# Schematic.net
KiCad netlist of a schematic drawn in EAGLE
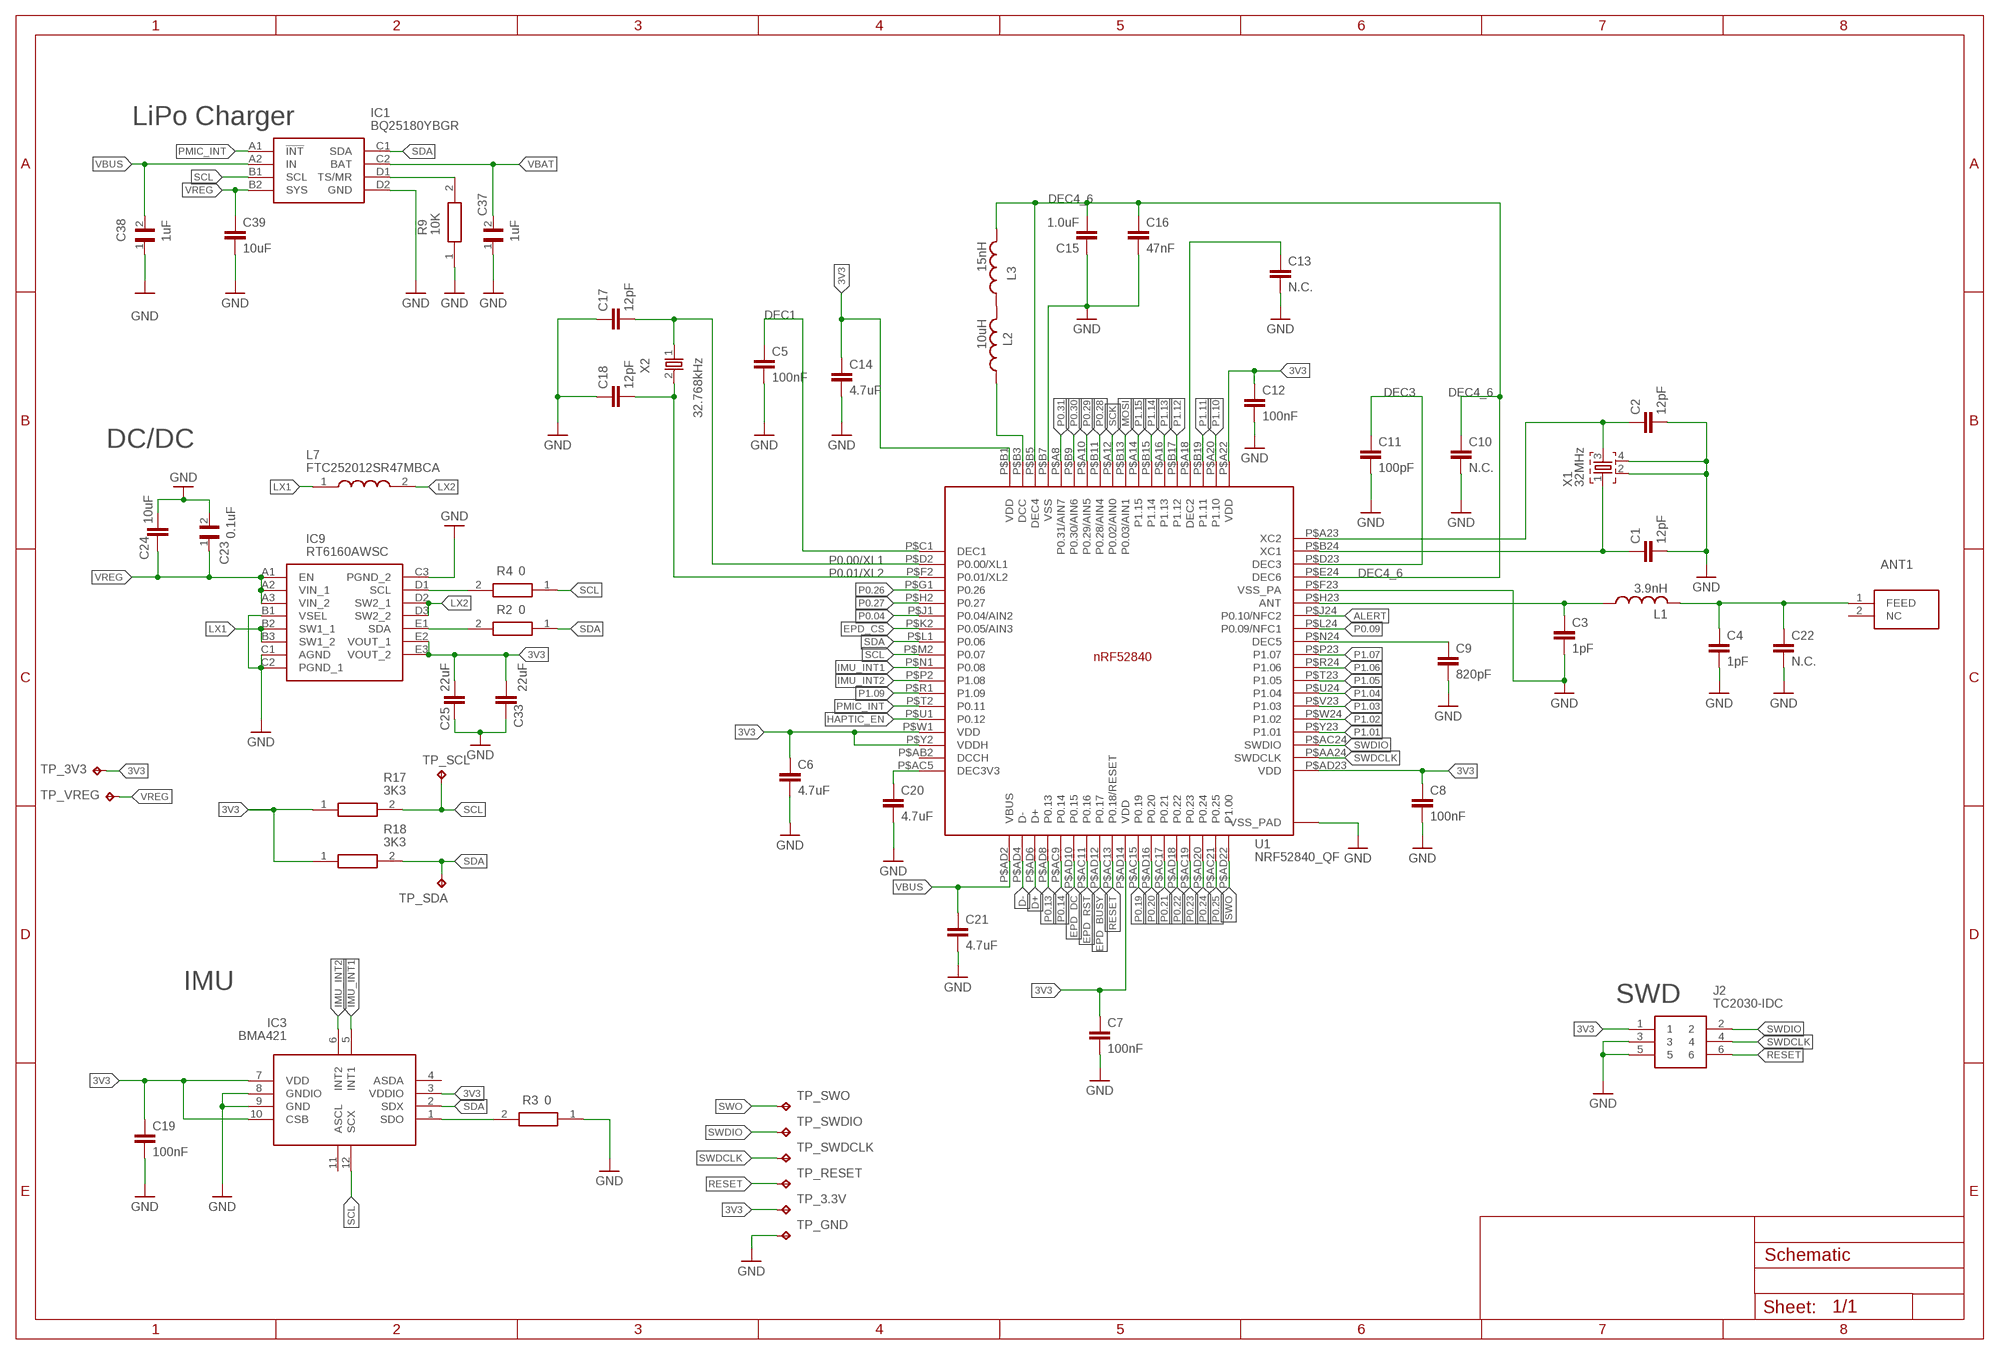
[diagram p0: schematic, sheet 1, part 1 of 2]
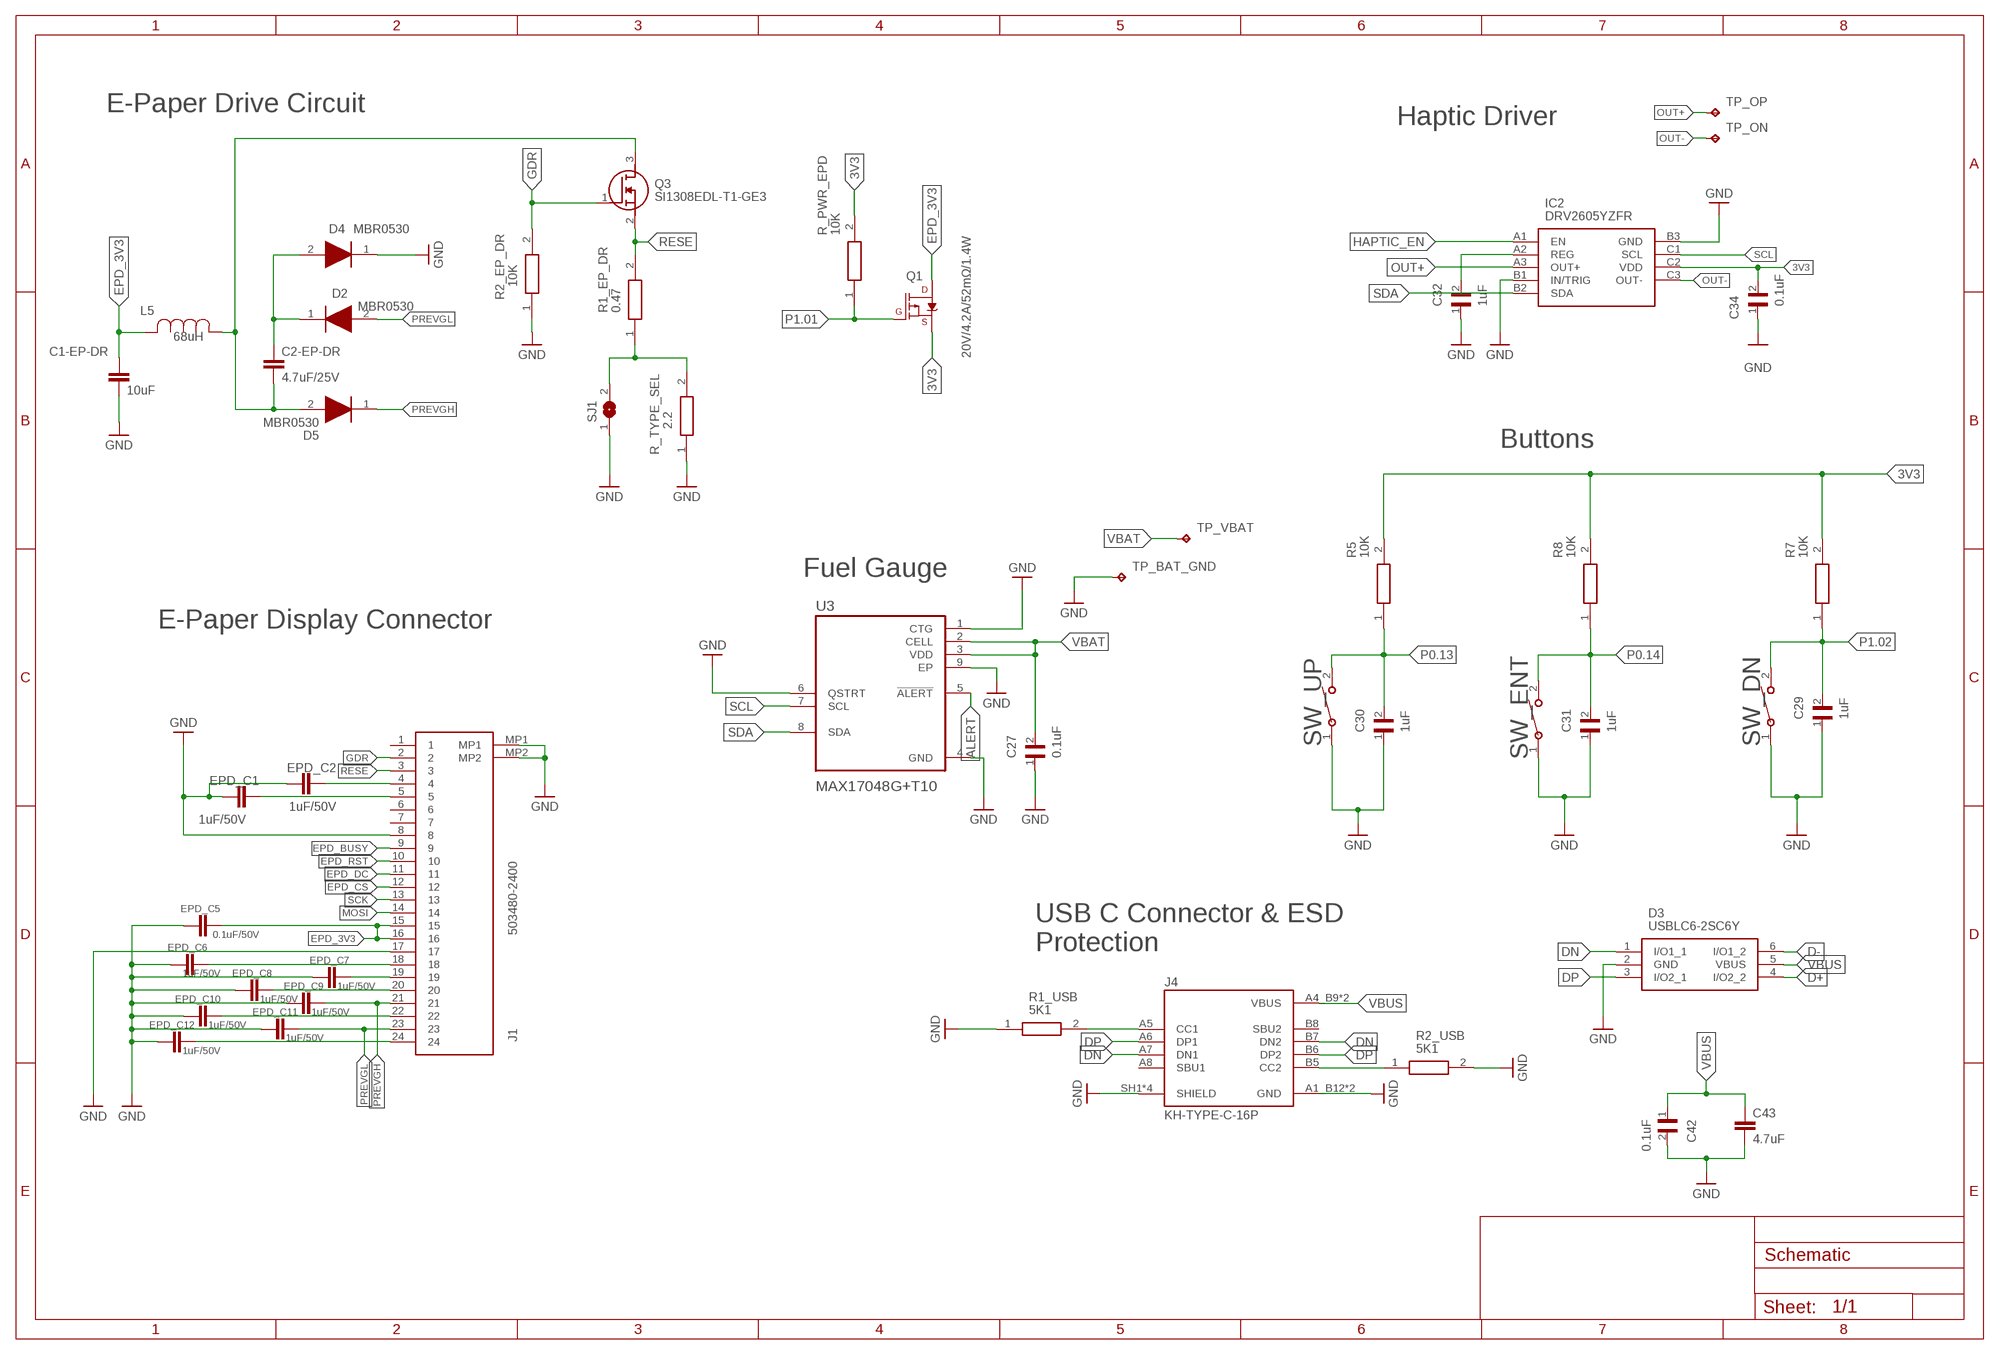
[diagram p1: schematic, sheet 1, part 2 of 2]

(export (version "E")
  (design (tool "Eeschema 10.0.6"))
  (components
    (comp (ref "ANT1")
      (value "2450AT18B100E_2450AT18B100E")
      (footprint "eagle-import:2450AT18B100E_ANTC3216X140N")
      (fields
        (field (name "ARROW_PART_NUMBER") "2450AT18B100E")
        (field (name "MOUSER_PART_NUMBER") "609-2450AT18B100E")
      )
      (libsource (lib "eagle-import") (part "2450AT18B100E_2450AT18B100E"))
    )
    (comp (ref "C1")
      (value "12pF")
      (footprint "eagle-import:PERFECT_0402_0402")
      (libsource (lib "eagle-import") (part "PERFECT_0402_CAP_0402"))
    )
    (comp (ref "C1-EP-DR")
      (value "10uF")
      (footprint "eagle-import:PERFECT_0402_0402")
      (libsource (lib "eagle-import") (part "PERFECT_0402_CAP_0402"))
    )
    (comp (ref "C2")
      (value "12pF")
      (footprint "eagle-import:PERFECT_0402_0402")
      (libsource (lib "eagle-import") (part "PERFECT_0402_CAP_0402"))
    )
    (comp (ref "C2-EP-DR")
      (value "4.7uF/25V")
      (footprint "eagle-import:PERFECT_0402_0402")
      (libsource (lib "eagle-import") (part "PERFECT_0402_CAP_0402"))
    )
    (comp (ref "C3")
      (value "1pF")
      (footprint "eagle-import:PERFECT_0402_0402")
      (libsource (lib "eagle-import") (part "PERFECT_0402_CAP_0402"))
    )
    (comp (ref "C4")
      (value "1pF")
      (footprint "eagle-import:PERFECT_0402_0402")
      (libsource (lib "eagle-import") (part "PERFECT_0402_CAP_0402"))
    )
    (comp (ref "C5")
      (value "100nF")
      (footprint "eagle-import:PERFECT_0402_0402")
      (libsource (lib "eagle-import") (part "PERFECT_0402_CAP_0402"))
    )
    (comp (ref "C6")
      (value "4.7uF")
      (footprint "eagle-import:PERFECT_0402_0402")
      (libsource (lib "eagle-import") (part "PERFECT_0402_CAP_0402"))
    )
    (comp (ref "C7")
      (value "100nF")
      (footprint "eagle-import:PERFECT_0402_0402")
      (libsource (lib "eagle-import") (part "PERFECT_0402_CAP_0402"))
    )
    (comp (ref "C8")
      (value "100nF")
      (footprint "eagle-import:PERFECT_0402_0402")
      (libsource (lib "eagle-import") (part "PERFECT_0402_CAP_0402"))
    )
    (comp (ref "C9")
      (value "820pF")
      (footprint "eagle-import:PERFECT_0402_0402")
      (libsource (lib "eagle-import") (part "PERFECT_0402_CAP_0402"))
    )
    (comp (ref "C10")
      (value "N.C.")
      (footprint "eagle-import:PERFECT_0402_0402")
      (libsource (lib "eagle-import") (part "PERFECT_0402_CAP_0402"))
    )
    (comp (ref "C11")
      (value "100pF")
      (footprint "eagle-import:PERFECT_0402_0402")
      (libsource (lib "eagle-import") (part "PERFECT_0402_CAP_0402"))
    )
    (comp (ref "C12")
      (value "100nF")
      (footprint "eagle-import:PERFECT_0402_0402")
      (libsource (lib "eagle-import") (part "PERFECT_0402_CAP_0402"))
    )
    (comp (ref "C13")
      (value "N.C.")
      (footprint "eagle-import:PERFECT_0402_0402")
      (libsource (lib "eagle-import") (part "PERFECT_0402_CAP_0402"))
    )
    (comp (ref "C14")
      (value "4.7uF")
      (footprint "eagle-import:PERFECT_0402_0402")
      (libsource (lib "eagle-import") (part "PERFECT_0402_CAP_0402"))
    )
    (comp (ref "C15")
      (value "1.0uF")
      (footprint "eagle-import:PERFECT_0402_0402")
      (libsource (lib "eagle-import") (part "PERFECT_0402_CAP_0402"))
    )
    (comp (ref "C16")
      (value "47nF")
      (footprint "eagle-import:PERFECT_0402_0402")
      (libsource (lib "eagle-import") (part "PERFECT_0402_CAP_0402"))
    )
    (comp (ref "C17")
      (value "12pF")
      (footprint "eagle-import:PERFECT_0402_0402")
      (libsource (lib "eagle-import") (part "PERFECT_0402_CAP_0402"))
    )
    (comp (ref "C18")
      (value "12pF")
      (footprint "eagle-import:PERFECT_0402_0402")
      (libsource (lib "eagle-import") (part "PERFECT_0402_CAP_0402"))
    )
    (comp (ref "C19")
      (value "100nF")
      (footprint "eagle-import:PERFECT_0402_0402")
      (libsource (lib "eagle-import") (part "PERFECT_0402_CAP_0402"))
    )
    (comp (ref "C20")
      (value "4.7uF")
      (footprint "eagle-import:PERFECT_0402_0402")
      (libsource (lib "eagle-import") (part "PERFECT_0402_CAP_0402"))
    )
    (comp (ref "C21")
      (value "4.7uF")
      (footprint "eagle-import:PERFECT_0402_0402")
      (libsource (lib "eagle-import") (part "PERFECT_0402_CAP_0402"))
    )
    (comp (ref "C22")
      (value "N.C.")
      (footprint "eagle-import:PERFECT_0402_0402")
      (libsource (lib "eagle-import") (part "PERFECT_0402_CAP_0402"))
    )
    (comp (ref "C23")
      (value "0.1uF")
      (footprint "eagle-import:GRM011R60J152KE01L_1_0201")
      (libsource (lib "eagle-import") (part "GRM011R60J152KE01L_1_GRM011R60J152KE01L"))
    )
    (comp (ref "C24")
      (value "10uF")
      (footprint "eagle-import:PERFECT_0402_0402")
      (libsource (lib "eagle-import") (part "PERFECT_0402_CAP_0402"))
    )
    (comp (ref "C25")
      (value "22uF")
      (footprint "eagle-import:PERFECT_0402_0402")
      (libsource (lib "eagle-import") (part "PERFECT_0402_CAP_0402"))
    )
    (comp (ref "C27")
      (value "0.1uF")
      (footprint "eagle-import:GRM011R60J152KE01L_1_0201")
      (libsource (lib "eagle-import") (part "InkTime_v5_vf.s9pZV0XdSHmKmdDjgWzDfQ_GRM011R60J152KE01L_1_GRM011R60J152KE01L"))
    )
    (comp (ref "C29")
      (value "1uF")
      (footprint "eagle-import:GRM011R60J152KE01L_1_0201")
      (libsource (lib "eagle-import") (part "GRM011R60J152KE01L_1_GRM011R60J152KE01L"))
    )
    (comp (ref "C30")
      (value "1uF")
      (footprint "eagle-import:GRM011R60J152KE01L_1_0201")
      (libsource (lib "eagle-import") (part "GRM011R60J152KE01L_1_GRM011R60J152KE01L"))
    )
    (comp (ref "C31")
      (value "1uF")
      (footprint "eagle-import:GRM011R60J152KE01L_1_0201")
      (libsource (lib "eagle-import") (part "GRM011R60J152KE01L_1_GRM011R60J152KE01L"))
    )
    (comp (ref "C32")
      (value "1uF")
      (footprint "eagle-import:GRM011R60J152KE01L_2_CAPC0201X13N")
      (fields (field (name "MF") "Murata") (field (name "MP") "GRM011R60J152KE01L"))
      (libsource (lib "eagle-import") (part "GRM011R60J152KE01L_2_GRM011R60J152KE01L"))
    )
    (comp (ref "C33")
      (value "22uF")
      (footprint "eagle-import:PERFECT_0402_0402")
      (libsource (lib "eagle-import") (part "PERFECT_0402_CAP_0402"))
    )
    (comp (ref "C34")
      (value "0.1uF")
      (footprint "eagle-import:GRM011R60J152KE01L_2_CAPC0201X13N")
      (fields (field (name "MF") "Murata") (field (name "MP") "GRM011R60J152KE01L"))
      (libsource (lib "eagle-import") (part "GRM011R60J152KE01L_2_GRM011R60J152KE01L"))
    )
    (comp (ref "C37")
      (value "1uF")
      (footprint "eagle-import:GRM011R60J152KE01L_1_0201")
      (libsource (lib "eagle-import") (part "GRM011R60J152KE01L_1_GRM011R60J152KE01L"))
    )
    (comp (ref "C38")
      (value "1uF")
      (footprint "eagle-import:GRM011R60J152KE01L_1_0201")
      (libsource (lib "eagle-import") (part "GRM011R60J152KE01L_1_GRM011R60J152KE01L"))
    )
    (comp (ref "C39")
      (value "10uF")
      (footprint "eagle-import:PERFECT_0402_0402")
      (libsource (lib "eagle-import") (part "PERFECT_0402_CAP_0402"))
    )
    (comp (ref "C42")
      (value "0.1uF")
      (footprint "eagle-import:GRM011R60J152KE01L_2_CAPC0201X13N")
      (fields (field (name "MF") "Murata") (field (name "MP") "GRM011R60J152KE01L"))
      (libsource (lib "eagle-import") (part "GRM011R60J152KE01L_2_GRM011R60J152KE01L"))
    )
    (comp (ref "C43")
      (value "4.7uF")
      (footprint "eagle-import:PERFECT_0402_0402")
      (libsource (lib "eagle-import") (part "PERFECT_0402_CAP_0402"))
    )
    (comp (ref "D2")
      (value "MBR0530")
      (footprint "eagle-import:ESP32_C6_LIBRARY_5_SOD3716X135N")
      (fields (field (name "MF") "ON Semiconductor"))
      (libsource (lib "eagle-import") (part "ESP32_C6_LIBRARY_5_MBR0530"))
    )
    (comp (ref "D3")
      (value "USBLC6-2SC6Y")
      (footprint "eagle-import:ESP32_C6_LIBRARY_3_SOT95P280X145-6N")
      (fields (field (name "MF") "STMicroelectronics"))
      (libsource (lib "eagle-import") (part "ESP32_C6_LIBRARY_3_USBLC6-2SC6Y"))
    )
    (comp (ref "D4")
      (value "MBR0530")
      (footprint "eagle-import:ESP32_C6_LIBRARY_5_SOD3716X135N")
      (fields (field (name "MF") "ON Semiconductor"))
      (libsource (lib "eagle-import") (part "ESP32_C6_LIBRARY_5_MBR0530"))
    )
    (comp (ref "D5")
      (value "MBR0530")
      (footprint "eagle-import:ESP32_C6_LIBRARY_5_SOD3716X135N")
      (fields (field (name "MF") "ON Semiconductor"))
      (libsource (lib "eagle-import") (part "ESP32_C6_LIBRARY_5_MBR0530"))
    )
    (comp (ref "EPD_C1")
      (value "1uF/50V")
      (footprint "eagle-import:NORDIC_NRF_3_RESC0201_L")
      (libsource (lib "eagle-import") (part "NORDIC_NRF_3_CAPACITOR_0201_L"))
    )
    (comp (ref "EPD_C2")
      (value "1uF/50V")
      (footprint "eagle-import:NORDIC_NRF_3_RESC0201_L")
      (libsource (lib "eagle-import") (part "NORDIC_NRF_3_CAPACITOR_0201_L"))
    )
    (comp (ref "EPD_C5")
      (value "0.1uF/50V")
      (footprint "eagle-import:NORDIC_NRF_3_RESC0201_L")
      (libsource (lib "eagle-import") (part "NORDIC_NRF_3_CAPACITOR_0201_L"))
    )
    (comp (ref "EPD_C6")
      (value "1uF/50V")
      (footprint "eagle-import:NORDIC_NRF_3_RESC0201_L")
      (libsource (lib "eagle-import") (part "NORDIC_NRF_3_CAPACITOR_0201_L"))
    )
    (comp (ref "EPD_C7")
      (value "1uF/50V")
      (footprint "eagle-import:NORDIC_NRF_3_RESC0201_L")
      (libsource (lib "eagle-import") (part "NORDIC_NRF_3_CAPACITOR_0201_L"))
    )
    (comp (ref "EPD_C8")
      (value "1uF/50V")
      (footprint "eagle-import:NORDIC_NRF_3_RESC0201_L")
      (libsource (lib "eagle-import") (part "NORDIC_NRF_3_CAPACITOR_0201_L"))
    )
    (comp (ref "EPD_C9")
      (value "1uF/50V")
      (footprint "eagle-import:NORDIC_NRF_3_RESC0201_L")
      (libsource (lib "eagle-import") (part "NORDIC_NRF_3_CAPACITOR_0201_L"))
    )
    (comp (ref "EPD_C10")
      (value "1uF/50V")
      (footprint "eagle-import:NORDIC_NRF_3_RESC0201_L")
      (libsource (lib "eagle-import") (part "NORDIC_NRF_3_CAPACITOR_0201_L"))
    )
    (comp (ref "EPD_C11")
      (value "1uF/50V")
      (footprint "eagle-import:NORDIC_NRF_3_RESC0201_L")
      (libsource (lib "eagle-import") (part "NORDIC_NRF_3_CAPACITOR_0201_L"))
    )
    (comp (ref "EPD_C12")
      (value "1uF/50V")
      (footprint "eagle-import:NORDIC_NRF_3_RESC0201_L")
      (libsource (lib "eagle-import") (part "NORDIC_NRF_3_CAPACITOR_0201_L"))
    )
    (comp (ref "IC1")
      (value "BQ25180YBGR")
      (footprint "eagle-import:BQ25180YBGR_BGA8C40P2X4_100X155X50")
      (fields (field (name "MOUSER_PART_NUMBER") "595-BQ25180YBGR"))
      (libsource (lib "eagle-import") (part "BQ25180YBGR_BQ25180YBGR"))
    )
    (comp (ref "IC2")
      (value "DRV2605YZFR")
      (footprint "eagle-import:DRV2605YZFR_BGA9C50P3X3_144X144X62")
      (libsource (lib "eagle-import") (part "DRV2605YZFR_DRV2605YZFR"))
    )
    (comp (ref "IC3")
      (value "BMA421")
      (footprint "eagle-import:BMA423_BMA423")
      (fields (field (name "ARROW_PART_NUMBER") "BMA423") (field (name "MOUSER_PART_NUMBER") "262-BMA423"))
      (libsource (lib "eagle-import") (part "BMA423_BMA423"))
    )
    (comp (ref "IC9")
      (value "RT6160AWSC")
      (footprint "eagle-import:RT6160AWSC_BGA15C40P3X5_140X230X60")
      (fields (field (name "MOUSER_PART_NUMBER") "835-RT6160AWSC"))
      (libsource (lib "eagle-import") (part "RT6160AWSC_RT6160AWSC"))
    )
    (comp (ref "J1")
      (value "503480-2400")
      (footprint "eagle-import:503480-2400_5034802400")
      (fields (field (name "MOUSER_PART_NUMBER") "538-503480-2400"))
      (libsource (lib "eagle-import") (part "503480-2400_503480-2400"))
    )
    (comp (ref "J2")
      (value "TC2030-IDC")
      (footprint "eagle-import:TC2030-IDC_TC2030IDC")
      (libsource (lib "eagle-import") (part "TC2030-IDC_TC2030-IDC"))
    )
    (comp (ref "J4")
      (value "KH-TYPE-C-16P")
      (footprint "eagle-import:KH-TYPE-C-16P_KINGHELM_KH-TYPE-C-16P")
      (fields (field (name "MF") "kinghelm"))
      (libsource (lib "eagle-import") (part "KH-TYPE-C-16P_KH-TYPE-C-16P"))
    )
    (comp (ref "L1")
      (value "3.9nH")
      (footprint "eagle-import:NORDIC_NRF_2_RESC0402_L")
      (libsource (lib "eagle-import") (part "NORDIC_NRF_2_INDUCTOR_0402_L"))
    )
    (comp (ref "L2")
      (value "10uH")
      (footprint "eagle-import:NORDIC_NRF_2_RESC0402_L")
      (libsource (lib "eagle-import") (part "NORDIC_NRF_2_INDUCTOR_0402_L"))
    )
    (comp (ref "L3")
      (value "15nH")
      (footprint "eagle-import:NORDIC_NRF_2_RESC0402_L")
      (libsource (lib "eagle-import") (part "NORDIC_NRF_2_INDUCTOR_0402_L"))
    )
    (comp (ref "L5")
      (value "68uH")
      (footprint "eagle-import:ESP32_C6_LIBRARY_2_IND_4828-WE-TPC_WRE")
      (fields
        (field (name "MANUFACTURER_PART_NUMBER") "744043680")
        (field (name "COPYRIGHT") "Copyright (C) 2024 Ultra Librarian. All rights reserved.")
      )
      (libsource (lib "eagle-import") (part "ESP32_C6_LIBRARY_2_744043680IND_4828-WE-TPC_WRE"))
    )
    (comp (ref "L7")
      (value "FTC252012SR47MBCA")
      (footprint "eagle-import:MLP2016SR47MT0S1_INDC2016X100N")
      (libsource (lib "eagle-import") (part "MLP2016SR47MT0S1_FTC252012SR47MBCA"))
    )
    (comp (ref "Q1")
      (value "20V/4.2A/52mΩ/1.4W")
      (footprint "eagle-import:ESP32_C6_LIBRARY_4_ESP32_C6_LIBRARY_4_ESP32_C6_LIBRARY_4_ESP32_C6_LIBRARY_4_ESP32_WROVER_SPARKFUN-DISCRETESEMI_SOT23-3")
      (libsource (lib "eagle-import") (part "ESP32_C6_LIBRARY_4_ESP32_WROVER_SPARKFUN-DISCRETESEMI_MOSFET_PCH-DMG2305UX-7"))
    )
    (comp (ref "Q3")
      (value "SI1308EDL-T1-GE3")
      (footprint "eagle-import:ESP32_C6_LIBRARY_6_SOT65P210X110-3N")
      (fields (field (name "MF") "Vishay Siliconix"))
      (libsource (lib "eagle-import") (part "ESP32_C6_LIBRARY_6_SI1308EDL-T1-GE3"))
    )
    (comp (ref "R1_EP_DR")
      (value "0.47")
      (footprint "eagle-import:CPF0201D7K68C1_0201")
      (libsource (lib "eagle-import") (part "CPF0201D7K68C1_CPF0201D7K68C1"))
    )
    (comp (ref "R1_USB")
      (value "5K1")
      (footprint "eagle-import:CPF0201D7K68C1_0201")
      (libsource (lib "eagle-import") (part "InkTime_v5_vf.s9pZV0XdSHmKmdDjgWzDfQ_CPF0201D7K68C1_CPF0201D7K68C1"))
    )
    (comp (ref "R2")
      (value "0")
      (footprint "eagle-import:ERA-1AEB3401C_0201")
      (libsource (lib "eagle-import") (part "InkTime_v5_vf.s9pZV0XdSHmKmdDjgWzDfQ_ERA-1AEB3401C_CPF0201D7K68C1"))
    )
    (comp (ref "R2_EP_DR")
      (value "10K")
      (footprint "eagle-import:CPF0201D7K68C1_0201")
      (libsource (lib "eagle-import") (part "CPF0201D7K68C1_CPF0201D7K68C1"))
    )
    (comp (ref "R2_USB")
      (value "5K1")
      (footprint "eagle-import:CPF0201D7K68C1_0201")
      (libsource (lib "eagle-import") (part "InkTime_v5_vf.s9pZV0XdSHmKmdDjgWzDfQ_CPF0201D7K68C1_CPF0201D7K68C1"))
    )
    (comp (ref "R3")
      (value "0")
      (footprint "eagle-import:ERA-1AEB3401C_0201")
      (libsource (lib "eagle-import") (part "ERA-1AEB3401C_CPF0201D7K68C1"))
    )
    (comp (ref "R4")
      (value "0")
      (footprint "eagle-import:ERA-1AEB3401C_0201")
      (libsource (lib "eagle-import") (part "ERA-1AEB3401C_CPF0201D7K68C1"))
    )
    (comp (ref "R5")
      (value "10K")
      (footprint "eagle-import:ERA-1AEB3401C_0201")
      (libsource (lib "eagle-import") (part "ERA-1AEB3401C_CPF0201D7K68C1"))
    )
    (comp (ref "R7")
      (value "10K")
      (footprint "eagle-import:ERA-1AEB3401C_0201")
      (libsource (lib "eagle-import") (part "ERA-1AEB3401C_CPF0201D7K68C1"))
    )
    (comp (ref "R8")
      (value "10K")
      (footprint "eagle-import:ERA-1AEB3401C_0201")
      (libsource (lib "eagle-import") (part "ERA-1AEB3401C_CPF0201D7K68C1"))
    )
    (comp (ref "R9")
      (value "10K")
      (footprint "eagle-import:CPF0201D7K68C1_0201")
      (libsource (lib "eagle-import") (part "CPF0201D7K68C1_CPF0201D7K68C1"))
    )
    (comp (ref "R17")
      (value "3K3")
      (footprint "eagle-import:ERA-1AEB3401C_0201")
      (libsource (lib "eagle-import") (part "ERA-1AEB3401C_CPF0201D7K68C1"))
    )
    (comp (ref "R18")
      (value "3K3")
      (footprint "eagle-import:ERA-1AEB3401C_0201")
      (libsource (lib "eagle-import") (part "ERA-1AEB3401C_CPF0201D7K68C1"))
    )
    (comp (ref "R_PWR_EPD")
      (value "10K")
      (footprint "eagle-import:ERA-1AEB3401C_0201")
      (libsource (lib "eagle-import") (part "ERA-1AEB3401C_CPF0201D7K68C1"))
    )
    (comp (ref "R_TYPE_SEL")
      (value "2.2")
      (footprint "eagle-import:CPF0201D7K68C1_0201")
      (libsource (lib "eagle-import") (part "CPF0201D7K68C1_CPF0201D7K68C1"))
    )
    (comp (ref "SJ1")
      (value "ESP32_C6_LIBRARY_7_JUMPER_SJ")
      (footprint "eagle-import:ESP32_C6_LIBRARY_7_JUMPER_SJ")
      (libsource (lib "eagle-import") (part "ESP32_C6_LIBRARY_7_JUMPER_SJ"))
    )
    (comp (ref "SW_DN")
      (value "2025-10-22_07-23-44_LIBRARY_EVP-AKE31ASW_EVP-AKE31A_PAN")
      (footprint "eagle-import:2025-10-22_07-23-44_LIBRARY_SW_EVP-AKE31A_PAN")
      (fields
        (field (name "MANUFACTURER_PART_NUMBER") "EVP-AKE31A")
        (field (name "COPYRIGHT") "Copyright (C) 2025 Ultra Librarian. All rights reserved.")
      )
      (libsource (lib "eagle-import") (part "2025-10-22_07-23-44_LIBRARY_EVP-AKE31ASW_EVP-AKE31A_PAN"))
    )
    (comp (ref "SW_ENT")
      (value "2025-10-22_07-23-44_LIBRARY_EVP-AKE31ASW_EVP-AKE31A_PAN")
      (footprint "eagle-import:2025-10-22_07-23-44_LIBRARY_SW_EVP-AKE31A_PAN")
      (fields
        (field (name "MANUFACTURER_PART_NUMBER") "EVP-AKE31A")
        (field (name "COPYRIGHT") "Copyright (C) 2025 Ultra Librarian. All rights reserved.")
      )
      (libsource (lib "eagle-import") (part "2025-10-22_07-23-44_LIBRARY_EVP-AKE31ASW_EVP-AKE31A_PAN"))
    )
    (comp (ref "SW_UP")
      (value "2025-10-22_07-23-44_LIBRARY_EVP-AKE31ASW_EVP-AKE31A_PAN")
      (footprint "eagle-import:2025-10-22_07-23-44_LIBRARY_SW_EVP-AKE31A_PAN")
      (fields
        (field (name "MANUFACTURER_PART_NUMBER") "EVP-AKE31A")
        (field (name "COPYRIGHT") "Copyright (C) 2025 Ultra Librarian. All rights reserved.")
      )
      (libsource (lib "eagle-import") (part "2025-10-22_07-23-44_LIBRARY_EVP-AKE31ASW_EVP-AKE31A_PAN"))
    )
    (comp (ref "TP_3.3V")
      (value "HECTOR_WATCH_1_TPTP20R")
      (footprint "eagle-import:HECTOR_WATCH_1_TP20R")
      (libsource (lib "eagle-import") (part "HECTOR_WATCH_1_TPTP20R"))
    )
    (comp (ref "TP_3V3")
      (value "HECTOR_WATCH_1_TPTP20R")
      (footprint "eagle-import:HECTOR_WATCH_1_TP20R")
      (libsource (lib "eagle-import") (part "HECTOR_WATCH_1_TPTP20R"))
    )
    (comp (ref "TP_BAT_GND")
      (value "HECTOR_WATCH_1_TPTP20R")
      (footprint "eagle-import:HECTOR_WATCH_1_TP20R")
      (libsource (lib "eagle-import") (part "HECTOR_WATCH_1_TPTP20R"))
    )
    (comp (ref "TP_GND")
      (value "HECTOR_WATCH_1_TPTP20R")
      (footprint "eagle-import:HECTOR_WATCH_1_TP20R")
      (libsource (lib "eagle-import") (part "HECTOR_WATCH_1_TPTP20R"))
    )
    (comp (ref "TP_ON")
      (value "HECTOR_WATCH_1_TPTP20R")
      (footprint "eagle-import:HECTOR_WATCH_1_TP20R")
      (libsource (lib "eagle-import") (part "HECTOR_WATCH_1_TPTP20R"))
    )
    (comp (ref "TP_OP")
      (value "HECTOR_WATCH_1_TPTP20R")
      (footprint "eagle-import:HECTOR_WATCH_1_TP20R")
      (libsource (lib "eagle-import") (part "HECTOR_WATCH_1_TPTP20R"))
    )
    (comp (ref "TP_RESET")
      (value "HECTOR_WATCH_1_TPTP20R")
      (footprint "eagle-import:HECTOR_WATCH_1_TP20R")
      (libsource (lib "eagle-import") (part "HECTOR_WATCH_1_TPTP20R"))
    )
    (comp (ref "TP_SCL")
      (value "HECTOR_WATCH_1_TPTP20R")
      (footprint "eagle-import:HECTOR_WATCH_1_TP20R")
      (libsource (lib "eagle-import") (part "HECTOR_WATCH_1_TPTP20R"))
    )
    (comp (ref "TP_SDA")
      (value "HECTOR_WATCH_1_TPTP20R")
      (footprint "eagle-import:HECTOR_WATCH_1_TP20R")
      (libsource (lib "eagle-import") (part "HECTOR_WATCH_1_TPTP20R"))
    )
    (comp (ref "TP_SWDCLK")
      (value "HECTOR_WATCH_1_TPTP20R")
      (footprint "eagle-import:HECTOR_WATCH_1_TP20R")
      (libsource (lib "eagle-import") (part "HECTOR_WATCH_1_TPTP20R"))
    )
    (comp (ref "TP_SWDIO")
      (value "HECTOR_WATCH_1_TPTP20R")
      (footprint "eagle-import:HECTOR_WATCH_1_TP20R")
      (libsource (lib "eagle-import") (part "HECTOR_WATCH_1_TPTP20R"))
    )
    (comp (ref "TP_SWO")
      (value "HECTOR_WATCH_1_TPTP20R")
      (footprint "eagle-import:HECTOR_WATCH_1_TP20R")
      (libsource (lib "eagle-import") (part "HECTOR_WATCH_1_TPTP20R"))
    )
    (comp (ref "TP_VBAT")
      (value "HECTOR_WATCH_1_TPTP20R")
      (footprint "eagle-import:HECTOR_WATCH_1_TP20R")
      (libsource (lib "eagle-import") (part "HECTOR_WATCH_1_TPTP20R"))
    )
    (comp (ref "TP_VREG")
      (value "HECTOR_WATCH_1_TPTP20R")
      (footprint "eagle-import:HECTOR_WATCH_1_TP20R")
      (libsource (lib "eagle-import") (part "HECTOR_WATCH_1_TPTP20R"))
    )
    (comp (ref "U1")
      (value "NRF52840_QF")
      (footprint "eagle-import:NORDIC_NRF_4_AQFN50P700X700X85_HS-74N")
      (libsource (lib "eagle-import") (part "NORDIC_NRF_4_NRF52840_QF"))
    )
    (comp (ref "U3")
      (value "MAX17048G+T10")
      (footprint "eagle-import:ESP32_C6_LIBRARY_SON50P200X200X80-9N")
      (fields (field (name "MF") "Analog Devices"))
      (libsource (lib "eagle-import") (part "ESP32_C6_LIBRARY_MAX17048G+T10"))
    )
    (comp (ref "X1")
      (value "32MHz")
      (footprint "eagle-import:NORDIC_NRF_BT-XTAL_2016_N")
      (libsource (lib "eagle-import") (part "NORDIC_NRF_XTAL_32MHZ"))
    )
    (comp (ref "X2")
      (value "32.768kHz")
      (footprint "eagle-import:NORDIC_NRF_1_XTAL_3215_N")
      (libsource (lib "eagle-import") (part "NORDIC_NRF_1_XTAL_32KHZ"))
    )
  )
  (nets
    (net (code "1") (name "3V3") (class "Default")
      (node (ref "C12") (pin "1") (pinfunction "1_1") (pintype "passive"))
      (node (ref "C14") (pin "1") (pinfunction "1_1") (pintype "passive"))
      (node (ref "C19") (pin "1") (pinfunction "1_1") (pintype "passive"))
      (node (ref "C25") (pin "1") (pinfunction "1_1") (pintype "passive"))
      (node (ref "C33") (pin "1") (pinfunction "1_1") (pintype "passive"))
      (node (ref "C34") (pin "2") (pinfunction "2_2") (pintype "passive"))
      (node (ref "C6") (pin "1") (pinfunction "1_1") (pintype "passive"))
      (node (ref "C7") (pin "1") (pinfunction "1_1") (pintype "passive"))
      (node (ref "C8") (pin "1") (pinfunction "1_1") (pintype "passive"))
      (node (ref "IC2") (pin "C2") (pinfunction "VDD_C2") (pintype "bidirectional"))
      (node (ref "IC3") (pin "10") (pinfunction "CSB_10") (pintype "bidirectional"))
      (node (ref "IC3") (pin "3") (pinfunction "VDDIO_3") (pintype "bidirectional"))
      (node (ref "IC3") (pin "7") (pinfunction "VDD_7") (pintype "bidirectional"))
      (node (ref "IC9") (pin "E2") (pinfunction "VOUT_1_E2") (pintype "bidirectional"))
      (node (ref "IC9") (pin "E3") (pinfunction "VOUT_2_E3") (pintype "bidirectional"))
      (node (ref "J2") (pin "1") (pinfunction "1_1") (pintype "bidirectional"))
      (node (ref "Q1") (pin "2") (pinfunction "S_2") (pintype "bidirectional"))
      (node (ref "R17") (pin "1") (pinfunction "1_1") (pintype "bidirectional"))
      (node (ref "R18") (pin "1") (pinfunction "1_1") (pintype "bidirectional"))
      (node (ref "R5") (pin "2") (pinfunction "2_2") (pintype "bidirectional"))
      (node (ref "R7") (pin "2") (pinfunction "2_2") (pintype "bidirectional"))
      (node (ref "R8") (pin "2") (pinfunction "2_2") (pintype "bidirectional"))
      (node (ref "R_PWR_EPD") (pin "2") (pinfunction "2_2") (pintype "bidirectional"))
      (node (ref "TP_3.3V") (pin "TP") (pinfunction "TP_TP") (pintype "input"))
      (node (ref "TP_3V3") (pin "TP") (pinfunction "TP_TP") (pintype "input"))
      (node (ref "U1") (pin "P$A22") (pinfunction "VDD_P$A22") (pintype "power_in"))
      (node (ref "U1") (pin "P$AD14") (pinfunction "VDD_P$AD14") (pintype "power_in"))
      (node (ref "U1") (pin "P$AD23") (pinfunction "VDD_P$AD23") (pintype "power_in"))
      (node (ref "U1") (pin "P$B1") (pinfunction "VDD_P$B1") (pintype "power_in"))
      (node (ref "U1") (pin "P$W1") (pinfunction "VDD_P$W1") (pintype "power_in"))
      (node (ref "U1") (pin "P$Y2") (pinfunction "VDDH_P$Y2") (pintype "power_in"))
    )
    (net (code "2") (name "ALERT") (class "Default")
      (node (ref "U1") (pin "P$J24") (pinfunction "P0.10/NFC2_P$J24") (pintype "bidirectional"))
      (node (ref "U3") (pin "5") (pinfunction "~{ALERT}_5") (pintype "output"))
    )
    (net (code "3") (name "D+") (class "Default")
      (node (ref "D3") (pin "4") (pinfunction "I/O2_2_4") (pintype "bidirectional"))
      (node (ref "U1") (pin "P$AD6") (pinfunction "D+_P$AD6") (pintype "bidirectional"))
    )
    (net (code "4") (name "D-") (class "Default")
      (node (ref "D3") (pin "6") (pinfunction "I/O1_2_6") (pintype "bidirectional"))
      (node (ref "U1") (pin "P$AD4") (pinfunction "D-_P$AD4") (pintype "bidirectional"))
    )
    (net (code "5") (name "DN") (class "Default")
      (node (ref "D3") (pin "1") (pinfunction "I/O1_1_1") (pintype "bidirectional"))
      (node (ref "J4") (pin "A7") (pinfunction "DN1_A7") (pintype "bidirectional"))
      (node (ref "J4") (pin "B7") (pinfunction "DN2_B7") (pintype "bidirectional"))
    )
    (net (code "6") (name "DP") (class "Default")
      (node (ref "D3") (pin "3") (pinfunction "I/O2_1_3") (pintype "bidirectional"))
      (node (ref "J4") (pin "A6") (pinfunction "DP1_A6") (pintype "bidirectional"))
      (node (ref "J4") (pin "B6") (pinfunction "DP2_B6") (pintype "bidirectional"))
    )
    (net (code "7") (name "EPD_3V3") (class "Default")
      (node (ref "C1-EP-DR") (pin "1") (pinfunction "1_1") (pintype "passive"))
      (node (ref "EPD_C5") (pin "2") (pinfunction "2_2") (pintype "passive"))
      (node (ref "J1") (pin "15") (pinfunction "15_15") (pintype "bidirectional"))
      (node (ref "J1") (pin "16") (pinfunction "16_16") (pintype "bidirectional"))
      (node (ref "L5") (pin "2") (pinfunction "2_2") (pintype "passive"))
      (node (ref "Q1") (pin "3") (pinfunction "D_3") (pintype "bidirectional"))
    )
    (net (code "8") (name "EPD_BUSY") (class "Default")
      (node (ref "J1") (pin "9") (pinfunction "9_9") (pintype "bidirectional"))
      (node (ref "U1") (pin "P$AD12") (pinfunction "P0.17_P$AD12") (pintype "bidirectional"))
    )
    (net (code "9") (name "EPD_CS") (class "Default")
      (node (ref "J1") (pin "12") (pinfunction "12_12") (pintype "bidirectional"))
      (node (ref "U1") (pin "P$K2") (pinfunction "P0.05/AIN3_P$K2") (pintype "bidirectional"))
    )
    (net (code "10") (name "EPD_DC") (class "Default")
      (node (ref "J1") (pin "11") (pinfunction "11_11") (pintype "bidirectional"))
      (node (ref "U1") (pin "P$AD10") (pinfunction "P0.15_P$AD10") (pintype "bidirectional"))
    )
    (net (code "11") (name "EPD_RST") (class "Default")
      (node (ref "J1") (pin "10") (pinfunction "10_10") (pintype "bidirectional"))
      (node (ref "U1") (pin "P$AC11") (pinfunction "P0.16_P$AC11") (pintype "bidirectional"))
    )
    (net (code "12") (name "GDR") (class "Default")
      (node (ref "J1") (pin "2") (pinfunction "2_2") (pintype "bidirectional"))
      (node (ref "Q3") (pin "1") (pinfunction "G_1") (pintype "bidirectional"))
      (node (ref "R2_EP_DR") (pin "2") (pinfunction "2_2") (pintype "bidirectional"))
    )
    (net (code "13") (name "GND") (class "Default")
      (node (ref "C1") (pin "2") (pinfunction "2_2") (pintype "passive"))
      (node (ref "C1-EP-DR") (pin "2") (pinfunction "2_2") (pintype "passive"))
      (node (ref "C10") (pin "2") (pinfunction "2_2") (pintype "passive"))
      (node (ref "C11") (pin "2") (pinfunction "2_2") (pintype "passive"))
      (node (ref "C12") (pin "2") (pinfunction "2_2") (pintype "passive"))
      (node (ref "C13") (pin "2") (pinfunction "2_2") (pintype "passive"))
      (node (ref "C14") (pin "2") (pinfunction "2_2") (pintype "passive"))
      (node (ref "C15") (pin "1") (pinfunction "1_1") (pintype "passive"))
      (node (ref "C16") (pin "2") (pinfunction "2_2") (pintype "passive"))
      (node (ref "C17") (pin "1") (pinfunction "1_1") (pintype "passive"))
      (node (ref "C18") (pin "1") (pinfunction "1_1") (pintype "passive"))
      (node (ref "C19") (pin "2") (pinfunction "2_2") (pintype "passive"))
      (node (ref "C2") (pin "2") (pinfunction "2_2") (pintype "passive"))
      (node (ref "C20") (pin "2") (pinfunction "2_2") (pintype "passive"))
      (node (ref "C21") (pin "2") (pinfunction "2_2") (pintype "passive"))
      (node (ref "C22") (pin "2") (pinfunction "2_2") (pintype "passive"))
      (node (ref "C23") (pin "2") (pinfunction "2_2") (pintype "passive"))
      (node (ref "C24") (pin "1") (pinfunction "1_1") (pintype "passive"))
      (node (ref "C25") (pin "2") (pinfunction "2_2") (pintype "passive"))
      (node (ref "C27") (pin "1") (pinfunction "1_1") (pintype "passive"))
      (node (ref "C29") (pin "1") (pinfunction "1_1") (pintype "passive"))
      (node (ref "C3") (pin "2") (pinfunction "2_2") (pintype "passive"))
      (node (ref "C30") (pin "1") (pinfunction "1_1") (pintype "passive"))
      (node (ref "C31") (pin "1") (pinfunction "1_1") (pintype "passive"))
      (node (ref "C32") (pin "1") (pinfunction "1_1") (pintype "passive"))
      (node (ref "C33") (pin "2") (pinfunction "2_2") (pintype "passive"))
      (node (ref "C34") (pin "1") (pinfunction "1_1") (pintype "passive"))
      (node (ref "C37") (pin "1") (pinfunction "1_1") (pintype "passive"))
      (node (ref "C38") (pin "1") (pinfunction "1_1") (pintype "passive"))
      (node (ref "C39") (pin "2") (pinfunction "2_2") (pintype "passive"))
      (node (ref "C4") (pin "2") (pinfunction "2_2") (pintype "passive"))
      (node (ref "C42") (pin "2") (pinfunction "2_2") (pintype "passive"))
      (node (ref "C43") (pin "2") (pinfunction "2_2") (pintype "passive"))
      (node (ref "C5") (pin "2") (pinfunction "2_2") (pintype "passive"))
      (node (ref "C6") (pin "2") (pinfunction "2_2") (pintype "passive"))
      (node (ref "C7") (pin "2") (pinfunction "2_2") (pintype "passive"))
      (node (ref "C8") (pin "2") (pinfunction "2_2") (pintype "passive"))
      (node (ref "C9") (pin "2") (pinfunction "2_2") (pintype "passive"))
      (node (ref "D3") (pin "2") (pinfunction "GND_2") (pintype "bidirectional"))
      (node (ref "D4") (pin "1") (pinfunction "K_1") (pintype "bidirectional"))
      (node (ref "EPD_C1") (pin "1") (pinfunction "1_1") (pintype "passive"))
      (node (ref "EPD_C10") (pin "1") (pinfunction "1_1") (pintype "passive"))
      (node (ref "EPD_C11") (pin "1") (pinfunction "1_1") (pintype "passive"))
      (node (ref "EPD_C12") (pin "1") (pinfunction "1_1") (pintype "passive"))
      (node (ref "EPD_C2") (pin "1") (pinfunction "1_1") (pintype "passive"))
      (node (ref "EPD_C5") (pin "1") (pinfunction "1_1") (pintype "passive"))
      (node (ref "EPD_C6") (pin "1") (pinfunction "1_1") (pintype "passive"))
      (node (ref "EPD_C7") (pin "1") (pinfunction "1_1") (pintype "passive"))
      (node (ref "EPD_C8") (pin "1") (pinfunction "1_1") (pintype "passive"))
      (node (ref "EPD_C9") (pin "1") (pinfunction "1_1") (pintype "passive"))
      (node (ref "IC1") (pin "D2") (pinfunction "GND_D2") (pintype "bidirectional"))
      (node (ref "IC2") (pin "B1") (pinfunction "IN/TRIG_B1") (pintype "bidirectional"))
      (node (ref "IC2") (pin "B3") (pinfunction "GND_B3") (pintype "bidirectional"))
      (node (ref "IC3") (pin "8") (pinfunction "GNDIO_8") (pintype "bidirectional"))
      (node (ref "IC3") (pin "9") (pinfunction "GND_9") (pintype "bidirectional"))
      (node (ref "IC9") (pin "B1") (pinfunction "VSEL_B1") (pintype "bidirectional"))
      (node (ref "IC9") (pin "C1") (pinfunction "AGND_C1") (pintype "bidirectional"))
      (node (ref "IC9") (pin "C2") (pinfunction "PGND_1_C2") (pintype "bidirectional"))
      (node (ref "IC9") (pin "C3") (pinfunction "PGND_2_C3") (pintype "bidirectional"))
      (node (ref "J1") (pin "17") (pinfunction "17_17") (pintype "bidirectional"))
      (node (ref "J1") (pin "8") (pinfunction "8_8") (pintype "bidirectional"))
      (node (ref "J1") (pin "MP1") (pinfunction "MP1_MP1") (pintype "bidirectional"))
      (node (ref "J1") (pin "MP2") (pinfunction "MP2_MP2") (pintype "bidirectional"))
      (node (ref "J2") (pin "3") (pinfunction "3_3") (pintype "bidirectional"))
      (node (ref "J2") (pin "5") (pinfunction "5_5") (pintype "bidirectional"))
      (node (ref "J4") (pin "A12_B1") (pinfunction "GND_A12_B1") (pintype "power_in"))
      (node (ref "J4") (pin "A1_B12") (pinfunction "GND_A1_B12") (pintype "power_in"))
      (node (ref "J4") (pin "SH1") (pinfunction "SHIELD_SH1") (pintype "passive"))
      (node (ref "J4") (pin "SH2") (pinfunction "SHIELD_SH2") (pintype "passive"))
      (node (ref "J4") (pin "SH3") (pinfunction "SHIELD_SH3") (pintype "passive"))
      (node (ref "J4") (pin "SH4") (pinfunction "SHIELD_SH4") (pintype "passive"))
      (node (ref "R1_USB") (pin "1") (pinfunction "1_1") (pintype "bidirectional"))
      (node (ref "R2_EP_DR") (pin "1") (pinfunction "1_1") (pintype "bidirectional"))
      (node (ref "R2_USB") (pin "2") (pinfunction "2_2") (pintype "bidirectional"))
      (node (ref "R3") (pin "1") (pinfunction "1_1") (pintype "bidirectional"))
      (node (ref "R9") (pin "1") (pinfunction "1_1") (pintype "bidirectional"))
      (node (ref "R_TYPE_SEL") (pin "1") (pinfunction "1_1") (pintype "bidirectional"))
      (node (ref "SJ1") (pin "1") (pinfunction "1_1") (pintype "passive"))
      (node (ref "SW_DN") (pin "1") (pinfunction "1_1") (pintype "passive"))
      (node (ref "SW_ENT") (pin "1") (pinfunction "1_1") (pintype "passive"))
      (node (ref "SW_UP") (pin "1") (pinfunction "1_1") (pintype "passive"))
      (node (ref "TP_BAT_GND") (pin "TP") (pinfunction "TP_TP") (pintype "input"))
      (node (ref "TP_GND") (pin "TP") (pinfunction "TP_TP") (pintype "input"))
      (node (ref "U1") (pin "P$74") (pinfunction "VSS_PAD_P$74") (pintype "bidirectional"))
      (node (ref "U1") (pin "P$75") (pinfunction "VSS_PAD_P$75") (pintype "bidirectional"))
      (node (ref "U1") (pin "P$76") (pinfunction "VSS_PAD_P$76") (pintype "bidirectional"))
      (node (ref "U1") (pin "P$77") (pinfunction "VSS_PAD_P$77") (pintype "bidirectional"))
      (node (ref "U1") (pin "P$78") (pinfunction "VSS_PAD_P$78") (pintype "bidirectional"))
      (node (ref "U1") (pin "P$79") (pinfunction "VSS_PAD_P$79") (pintype "bidirectional"))
      (node (ref "U1") (pin "P$80") (pinfunction "VSS_PAD_P$80") (pintype "bidirectional"))
      (node (ref "U1") (pin "P$81") (pinfunction "VSS_PAD_P$81") (pintype "bidirectional"))
      (node (ref "U1") (pin "P$82") (pinfunction "VSS_PAD_P$82") (pintype "bidirectional"))
      (node (ref "U1") (pin "P$83") (pinfunction "VSS_PAD_P$83") (pintype "bidirectional"))
      (node (ref "U1") (pin "P$84") (pinfunction "VSS_PAD_P$84") (pintype "bidirectional"))
      (node (ref "U1") (pin "P$85") (pinfunction "VSS_PAD_P$85") (pintype "bidirectional"))
      (node (ref "U1") (pin "P$86") (pinfunction "VSS_PAD_P$86") (pintype "bidirectional"))
      (node (ref "U1") (pin "P$87") (pinfunction "VSS_PAD_P$87") (pintype "bidirectional"))
      (node (ref "U1") (pin "P$88") (pinfunction "VSS_PAD_P$88") (pintype "bidirectional"))
      (node (ref "U1") (pin "P$89") (pinfunction "VSS_PAD_P$89") (pintype "bidirectional"))
      (node (ref "U1") (pin "P$90") (pinfunction "VSS_PAD_P$90") (pintype "bidirectional"))
      (node (ref "U1") (pin "P$B7") (pinfunction "VSS_P$B7") (pintype "power_in"))
      (node (ref "U1") (pin "P$F23") (pinfunction "VSS_PA_P$F23") (pintype "bidirectional"))
      (node (ref "U3") (pin "1") (pinfunction "CTG_1") (pintype "power_in"))
      (node (ref "U3") (pin "4") (pinfunction "GND_4") (pintype "power_in"))
      (node (ref "U3") (pin "6") (pinfunction "QSTRT_6") (pintype "input"))
      (node (ref "U3") (pin "9") (pinfunction "EP_9") (pintype "power_in"))
      (node (ref "X1") (pin "2") (pinfunction "2_2") (pintype "passive"))
      (node (ref "X1") (pin "4") (pinfunction "4_4") (pintype "passive"))
    )
    (net (code "14") (name "HAPTIC_EN") (class "Default")
      (node (ref "IC2") (pin "A1") (pinfunction "EN_A1") (pintype "bidirectional"))
      (node (ref "U1") (pin "P$U1") (pinfunction "P0.12_P$U1") (pintype "bidirectional"))
    )
    (net (code "15") (name "IMU_INT1") (class "Default")
      (node (ref "IC3") (pin "5") (pinfunction "INT1_5") (pintype "bidirectional"))
      (node (ref "U1") (pin "P$N1") (pinfunction "P0.08_P$N1") (pintype "bidirectional"))
    )
    (net (code "16") (name "IMU_INT2") (class "Default")
      (node (ref "IC3") (pin "6") (pinfunction "INT2_6") (pintype "bidirectional"))
      (node (ref "U1") (pin "P$P2") (pinfunction "P1.08_P$P2") (pintype "bidirectional"))
    )
    (net (code "17") (name "LX1") (class "Default")
      (node (ref "IC9") (pin "B2") (pinfunction "SW1_1_B2") (pintype "bidirectional"))
      (node (ref "IC9") (pin "B3") (pinfunction "SW1_2_B3") (pintype "bidirectional"))
      (node (ref "L7") (pin "1") (pinfunction "1_1") (pintype "bidirectional"))
    )
    (net (code "18") (name "LX2") (class "Default")
      (node (ref "IC9") (pin "D2") (pinfunction "SW2_1_D2") (pintype "bidirectional"))
      (node (ref "IC9") (pin "D3") (pinfunction "SW2_2_D3") (pintype "bidirectional"))
      (node (ref "L7") (pin "2") (pinfunction "2_2") (pintype "bidirectional"))
    )
    (net (code "19") (name "MOSI") (class "Default")
      (node (ref "J1") (pin "14") (pinfunction "14_14") (pintype "bidirectional"))
      (node (ref "U1") (pin "P$B13") (pinfunction "P0.03/AIN1_P$B13") (pintype "bidirectional"))
    )
    (net (code "20") (name "Net-(ANT1-FEED)") (class "Default")
      (node (ref "ANT1") (pin "1") (pinfunction "FEED_1") (pintype "input"))
      (node (ref "C22") (pin "1") (pinfunction "1_1") (pintype "passive"))
      (node (ref "C4") (pin "1") (pinfunction "1_1") (pintype "passive"))
      (node (ref "L1") (pin "2") (pinfunction "2_2") (pintype "passive"))
    )
    (net (code "21") (name "Net-(D2-K)") (class "Default")
      (node (ref "C2-EP-DR") (pin "1") (pinfunction "1_1") (pintype "passive"))
      (node (ref "D2") (pin "1") (pinfunction "K_1") (pintype "bidirectional"))
      (node (ref "D4") (pin "2") (pinfunction "A_2") (pintype "bidirectional"))
    )
    (net (code "22") (name "Net-(D5-A)") (class "Default")
      (node (ref "C2-EP-DR") (pin "2") (pinfunction "2_2") (pintype "passive"))
      (node (ref "D5") (pin "2") (pinfunction "A_2") (pintype "bidirectional"))
      (node (ref "L5") (pin "1") (pinfunction "1_1") (pintype "passive"))
      (node (ref "Q3") (pin "3") (pinfunction "D_3") (pintype "bidirectional"))
    )
    (net (code "23") (name "Net-(EPD_C1-Pad2)") (class "Default")
      (node (ref "EPD_C1") (pin "2") (pinfunction "2_2") (pintype "passive"))
      (node (ref "J1") (pin "5") (pinfunction "5_5") (pintype "bidirectional"))
    )
    (net (code "24") (name "Net-(EPD_C2-Pad2)") (class "Default")
      (node (ref "EPD_C2") (pin "2") (pinfunction "2_2") (pintype "passive"))
      (node (ref "J1") (pin "4") (pinfunction "4_4") (pintype "bidirectional"))
    )
    (net (code "25") (name "Net-(EPD_C6-Pad2)") (class "Default")
      (node (ref "EPD_C6") (pin "2") (pinfunction "2_2") (pintype "passive"))
      (node (ref "J1") (pin "18") (pinfunction "18_18") (pintype "bidirectional"))
    )
    (net (code "26") (name "Net-(EPD_C7-Pad2)") (class "Default")
      (node (ref "EPD_C7") (pin "2") (pinfunction "2_2") (pintype "passive"))
      (node (ref "J1") (pin "19") (pinfunction "19_19") (pintype "bidirectional"))
    )
    (net (code "27") (name "Net-(EPD_C8-Pad2)") (class "Default")
      (node (ref "EPD_C8") (pin "2") (pinfunction "2_2") (pintype "passive"))
      (node (ref "J1") (pin "20") (pinfunction "20_20") (pintype "bidirectional"))
    )
    (net (code "28") (name "Net-(EPD_C10-Pad2)") (class "Default")
      (node (ref "EPD_C10") (pin "2") (pinfunction "2_2") (pintype "passive"))
      (node (ref "J1") (pin "22") (pinfunction "22_22") (pintype "bidirectional"))
    )
    (net (code "29") (name "Net-(EPD_C12-Pad2)") (class "Default")
      (node (ref "EPD_C12") (pin "2") (pinfunction "2_2") (pintype "passive"))
      (node (ref "J1") (pin "24") (pinfunction "24_24") (pintype "bidirectional"))
    )
    (net (code "30") (name "Net-(IC1-TS{slash}MR)") (class "Default")
      (node (ref "IC1") (pin "D1") (pinfunction "TS/MR_D1") (pintype "bidirectional"))
      (node (ref "R9") (pin "2") (pinfunction "2_2") (pintype "bidirectional"))
    )
    (net (code "31") (name "Net-(IC2-REG)") (class "Default")
      (node (ref "C32") (pin "2") (pinfunction "2_2") (pintype "passive"))
      (node (ref "IC2") (pin "A2") (pinfunction "REG_A2") (pintype "bidirectional"))
    )
    (net (code "32") (name "Net-(IC3-SDO)") (class "Default")
      (node (ref "IC3") (pin "1") (pinfunction "SDO_1") (pintype "bidirectional"))
      (node (ref "R3") (pin "2") (pinfunction "2_2") (pintype "bidirectional"))
    )
    (net (code "33") (name "Net-(IC9-SCL)") (class "Default")
      (node (ref "IC9") (pin "D1") (pinfunction "SCL_D1") (pintype "bidirectional"))
      (node (ref "R4") (pin "2") (pinfunction "2_2") (pintype "bidirectional"))
    )
    (net (code "34") (name "Net-(IC9-SDA)") (class "Default")
      (node (ref "IC9") (pin "E1") (pinfunction "SDA_E1") (pintype "bidirectional"))
      (node (ref "R2") (pin "2") (pinfunction "2_2") (pintype "bidirectional"))
    )
    (net (code "35") (name "Net-(J4-CC1)") (class "Default")
      (node (ref "J4") (pin "A5") (pinfunction "CC1_A5") (pintype "bidirectional"))
      (node (ref "R1_USB") (pin "2") (pinfunction "2_2") (pintype "bidirectional"))
    )
    (net (code "36") (name "Net-(J4-CC2)") (class "Default")
      (node (ref "J4") (pin "B5") (pinfunction "CC2_B5") (pintype "bidirectional"))
      (node (ref "R2_USB") (pin "1") (pinfunction "1_1") (pintype "bidirectional"))
    )
    (net (code "37") (name "Net-(L2-Pad2)") (class "Default")
      (node (ref "L2") (pin "2") (pinfunction "2_2") (pintype "passive"))
      (node (ref "L3") (pin "1") (pinfunction "1_1") (pintype "passive"))
    )
    (net (code "38") (name "Net-(R1_EP_DR-Pad1)") (class "Default")
      (node (ref "R1_EP_DR") (pin "1") (pinfunction "1_1") (pintype "bidirectional"))
      (node (ref "R_TYPE_SEL") (pin "2") (pinfunction "2_2") (pintype "bidirectional"))
      (node (ref "SJ1") (pin "2") (pinfunction "2_2") (pintype "passive"))
    )
    (net (code "39") (name "Net-(U1-ANT)") (class "Default")
      (node (ref "C3") (pin "1") (pinfunction "1_1") (pintype "passive"))
      (node (ref "L1") (pin "1") (pinfunction "1_1") (pintype "passive"))
      (node (ref "U1") (pin "P$H23") (pinfunction "ANT_P$H23") (pintype "bidirectional"))
    )
    (net (code "40") (name "Net-(U1-DCC)") (class "Default")
      (node (ref "L2") (pin "1") (pinfunction "1_1") (pintype "passive"))
      (node (ref "U1") (pin "P$B3") (pinfunction "DCC_P$B3") (pintype "output"))
    )
    (net (code "41") (name "Net-(U1-DEC1)") (class "Default")
      (node (ref "C5") (pin "1") (pinfunction "1_1") (pintype "passive"))
      (node (ref "U1") (pin "P$C1") (pinfunction "DEC1_P$C1") (pintype "power_in"))
    )
    (net (code "42") (name "Net-(U1-DEC2)") (class "Default")
      (node (ref "C13") (pin "1") (pinfunction "1_1") (pintype "passive"))
      (node (ref "U1") (pin "P$A18") (pinfunction "DEC2_P$A18") (pintype "bidirectional"))
    )
    (net (code "43") (name "Net-(U1-DEC3)") (class "Default")
      (node (ref "C11") (pin "1") (pinfunction "1_1") (pintype "passive"))
      (node (ref "U1") (pin "P$D23") (pinfunction "DEC3_P$D23") (pintype "bidirectional"))
    )
    (net (code "44") (name "Net-(U1-DEC3V3)") (class "Default")
      (node (ref "C20") (pin "1") (pinfunction "1_1") (pintype "passive"))
      (node (ref "U1") (pin "P$AC5") (pinfunction "DEC3V3_P$AC5") (pintype "bidirectional"))
    )
    (net (code "45") (name "Net-(U1-DEC4)") (class "Default")
      (node (ref "C10") (pin "1") (pinfunction "1_1") (pintype "passive"))
      (node (ref "C15") (pin "2") (pinfunction "2_2") (pintype "passive"))
      (node (ref "C16") (pin "1") (pinfunction "1_1") (pintype "passive"))
      (node (ref "L3") (pin "2") (pinfunction "2_2") (pintype "passive"))
      (node (ref "U1") (pin "P$B5") (pinfunction "DEC4_P$B5") (pintype "power_in"))
      (node (ref "U1") (pin "P$E24") (pinfunction "DEC6_P$E24") (pintype "bidirectional"))
    )
    (net (code "46") (name "Net-(U1-DEC5)") (class "Default")
      (node (ref "C9") (pin "1") (pinfunction "1_1") (pintype "passive"))
      (node (ref "U1") (pin "P$N24") (pinfunction "DEC5_P$N24") (pintype "bidirectional"))
    )
    (net (code "47") (name "Net-(U1-P0.00{slash}XL1)") (class "Default")
      (node (ref "C17") (pin "2") (pinfunction "2_2") (pintype "passive"))
      (node (ref "U1") (pin "P$D2") (pinfunction "P0.00/XL1_P$D2") (pintype "bidirectional"))
      (node (ref "X2") (pin "1") (pinfunction "1_1") (pintype "passive"))
    )
    (net (code "48") (name "Net-(U1-P0.01{slash}XL2)") (class "Default")
      (node (ref "C18") (pin "2") (pinfunction "2_2") (pintype "passive"))
      (node (ref "U1") (pin "P$F2") (pinfunction "P0.01/XL2_P$F2") (pintype "bidirectional"))
      (node (ref "X2") (pin "2") (pinfunction "2_2") (pintype "passive"))
    )
    (net (code "49") (name "Net-(U1-XC1)") (class "Default")
      (node (ref "C1") (pin "1") (pinfunction "1_1") (pintype "passive"))
      (node (ref "U1") (pin "P$B24") (pinfunction "XC1_P$B24") (pintype "input"))
      (node (ref "X1") (pin "1") (pinfunction "1_1") (pintype "passive"))
    )
    (net (code "50") (name "Net-(U1-XC2)") (class "Default")
      (node (ref "C2") (pin "1") (pinfunction "1_1") (pintype "passive"))
      (node (ref "U1") (pin "P$A23") (pinfunction "XC2_P$A23") (pintype "output"))
      (node (ref "X1") (pin "3") (pinfunction "3_3") (pintype "passive"))
    )
    (net (code "51") (name "OUT+") (class "Default")
      (node (ref "IC2") (pin "A3") (pinfunction "OUT+_A3") (pintype "bidirectional"))
      (node (ref "TP_OP") (pin "TP") (pinfunction "TP_TP") (pintype "input"))
    )
    (net (code "52") (name "OUT-") (class "Default")
      (node (ref "IC2") (pin "C3") (pinfunction "OUT-_C3") (pintype "bidirectional"))
      (node (ref "TP_ON") (pin "TP") (pinfunction "TP_TP") (pintype "input"))
    )
    (net (code "53") (name "P0.04") (class "Default")
      (node (ref "U1") (pin "P$J1") (pinfunction "P0.04/AIN2_P$J1") (pintype "bidirectional"))
    )
    (net (code "54") (name "P0.09") (class "Default")
      (node (ref "U1") (pin "P$L24") (pinfunction "P0.09/NFC1_P$L24") (pintype "bidirectional"))
    )
    (net (code "55") (name "P0.13") (class "Default")
      (node (ref "C30") (pin "2") (pinfunction "2_2") (pintype "passive"))
      (node (ref "R5") (pin "1") (pinfunction "1_1") (pintype "bidirectional"))
      (node (ref "SW_UP") (pin "2") (pinfunction "2_2") (pintype "passive"))
      (node (ref "U1") (pin "P$AD8") (pinfunction "P0.13_P$AD8") (pintype "bidirectional"))
    )
    (net (code "56") (name "P0.14") (class "Default")
      (node (ref "C31") (pin "2") (pinfunction "2_2") (pintype "passive"))
      (node (ref "R8") (pin "1") (pinfunction "1_1") (pintype "bidirectional"))
      (node (ref "SW_ENT") (pin "2") (pinfunction "2_2") (pintype "passive"))
      (node (ref "U1") (pin "P$AC9") (pinfunction "P0.14_P$AC9") (pintype "bidirectional"))
    )
    (net (code "57") (name "P0.19") (class "Default")
      (node (ref "U1") (pin "P$AC15") (pinfunction "P0.19_P$AC15") (pintype "bidirectional"))
    )
    (net (code "58") (name "P0.20") (class "Default")
      (node (ref "U1") (pin "P$AD16") (pinfunction "P0.20_P$AD16") (pintype "bidirectional"))
    )
    (net (code "59") (name "P0.21") (class "Default")
      (node (ref "U1") (pin "P$AC17") (pinfunction "P0.21_P$AC17") (pintype "bidirectional"))
    )
    (net (code "60") (name "P0.22") (class "Default")
      (node (ref "U1") (pin "P$AD18") (pinfunction "P0.22_P$AD18") (pintype "bidirectional"))
    )
    (net (code "61") (name "P0.23") (class "Default")
      (node (ref "U1") (pin "P$AC19") (pinfunction "P0.23_P$AC19") (pintype "bidirectional"))
    )
    (net (code "62") (name "P0.24") (class "Default")
      (node (ref "U1") (pin "P$AD20") (pinfunction "P0.24_P$AD20") (pintype "bidirectional"))
    )
    (net (code "63") (name "P0.25") (class "Default")
      (node (ref "U1") (pin "P$AC21") (pinfunction "P0.25_P$AC21") (pintype "bidirectional"))
    )
    (net (code "64") (name "P0.26") (class "Default")
      (node (ref "U1") (pin "P$G1") (pinfunction "P0.26_P$G1") (pintype "bidirectional"))
    )
    (net (code "65") (name "P0.27") (class "Default")
      (node (ref "U1") (pin "P$H2") (pinfunction "P0.27_P$H2") (pintype "bidirectional"))
    )
    (net (code "66") (name "P0.28") (class "Default")
      (node (ref "U1") (pin "P$B11") (pinfunction "P0.28/AIN4_P$B11") (pintype "bidirectional"))
    )
    (net (code "67") (name "P0.29") (class "Default")
      (node (ref "U1") (pin "P$A10") (pinfunction "P0.29/AIN5_P$A10") (pintype "bidirectional"))
    )
    (net (code "68") (name "P0.30") (class "Default")
      (node (ref "U1") (pin "P$B9") (pinfunction "P0.30/AIN6_P$B9") (pintype "bidirectional"))
    )
    (net (code "69") (name "P0.31") (class "Default")
      (node (ref "U1") (pin "P$A8") (pinfunction "P0.31/AIN7_P$A8") (pintype "bidirectional"))
    )
    (net (code "70") (name "P1.01") (class "Default")
      (node (ref "Q1") (pin "1") (pinfunction "G_1") (pintype "bidirectional"))
      (node (ref "R_PWR_EPD") (pin "1") (pinfunction "1_1") (pintype "bidirectional"))
      (node (ref "U1") (pin "P$Y23") (pinfunction "P1.01_P$Y23") (pintype "bidirectional"))
    )
    (net (code "71") (name "P1.02") (class "Default")
      (node (ref "C29") (pin "2") (pinfunction "2_2") (pintype "passive"))
      (node (ref "R7") (pin "1") (pinfunction "1_1") (pintype "bidirectional"))
      (node (ref "SW_DN") (pin "2") (pinfunction "2_2") (pintype "passive"))
      (node (ref "U1") (pin "P$W24") (pinfunction "P1.02_P$W24") (pintype "bidirectional"))
    )
    (net (code "72") (name "P1.03") (class "Default")
      (node (ref "U1") (pin "P$V23") (pinfunction "P1.03_P$V23") (pintype "bidirectional"))
    )
    (net (code "73") (name "P1.04") (class "Default")
      (node (ref "U1") (pin "P$U24") (pinfunction "P1.04_P$U24") (pintype "bidirectional"))
    )
    (net (code "74") (name "P1.05") (class "Default")
      (node (ref "U1") (pin "P$T23") (pinfunction "P1.05_P$T23") (pintype "bidirectional"))
    )
    (net (code "75") (name "P1.06") (class "Default")
      (node (ref "U1") (pin "P$R24") (pinfunction "P1.06_P$R24") (pintype "bidirectional"))
    )
    (net (code "76") (name "P1.07") (class "Default")
      (node (ref "U1") (pin "P$P23") (pinfunction "P1.07_P$P23") (pintype "bidirectional"))
    )
    (net (code "77") (name "P1.09") (class "Default")
      (node (ref "U1") (pin "P$R1") (pinfunction "P1.09_P$R1") (pintype "bidirectional"))
    )
    (net (code "78") (name "P1.10") (class "Default")
      (node (ref "U1") (pin "P$A20") (pinfunction "P1.10_P$A20") (pintype "bidirectional"))
    )
    (net (code "79") (name "P1.11") (class "Default")
      (node (ref "U1") (pin "P$B19") (pinfunction "P1.11_P$B19") (pintype "bidirectional"))
    )
    (net (code "80") (name "P1.12") (class "Default")
      (node (ref "U1") (pin "P$B17") (pinfunction "P1.12_P$B17") (pintype "bidirectional"))
    )
    (net (code "81") (name "P1.13") (class "Default")
      (node (ref "U1") (pin "P$A16") (pinfunction "P1.13_P$A16") (pintype "bidirectional"))
    )
    (net (code "82") (name "P1.14") (class "Default")
      (node (ref "U1") (pin "P$B15") (pinfunction "P1.14_P$B15") (pintype "bidirectional"))
    )
    (net (code "83") (name "P1.15") (class "Default")
      (node (ref "U1") (pin "P$A14") (pinfunction "P1.15_P$A14") (pintype "bidirectional"))
    )
    (net (code "84") (name "PMIC_INT") (class "Default")
      (node (ref "IC1") (pin "A1") (pinfunction "~{INT}_A1") (pintype "bidirectional"))
      (node (ref "U1") (pin "P$T2") (pinfunction "P0.11_P$T2") (pintype "bidirectional"))
    )
    (net (code "85") (name "PREVGH") (class "Default")
      (node (ref "D5") (pin "1") (pinfunction "K_1") (pintype "bidirectional"))
      (node (ref "EPD_C9") (pin "2") (pinfunction "2_2") (pintype "passive"))
      (node (ref "J1") (pin "21") (pinfunction "21_21") (pintype "bidirectional"))
    )
    (net (code "86") (name "PREVGL") (class "Default")
      (node (ref "D2") (pin "2") (pinfunction "A_2") (pintype "bidirectional"))
      (node (ref "EPD_C11") (pin "2") (pinfunction "2_2") (pintype "passive"))
      (node (ref "J1") (pin "23") (pinfunction "23_23") (pintype "bidirectional"))
    )
    (net (code "87") (name "RESE") (class "Default")
      (node (ref "J1") (pin "3") (pinfunction "3_3") (pintype "bidirectional"))
      (node (ref "Q3") (pin "2") (pinfunction "S_2") (pintype "bidirectional"))
      (node (ref "R1_EP_DR") (pin "2") (pinfunction "2_2") (pintype "bidirectional"))
    )
    (net (code "88") (name "RESET") (class "Default")
      (node (ref "J2") (pin "6") (pinfunction "6_6") (pintype "bidirectional"))
      (node (ref "TP_RESET") (pin "TP") (pinfunction "TP_TP") (pintype "input"))
      (node (ref "U1") (pin "P$AC13") (pinfunction "P0.18/RESET_P$AC13") (pintype "bidirectional"))
    )
    (net (code "89") (name "SCK") (class "Default")
      (node (ref "J1") (pin "13") (pinfunction "13_13") (pintype "bidirectional"))
      (node (ref "U1") (pin "P$A12") (pinfunction "P0.02/AIN0_P$A12") (pintype "bidirectional"))
    )
    (net (code "90") (name "SCL") (class "Default")
      (node (ref "IC1") (pin "B1") (pinfunction "SCL_B1") (pintype "bidirectional"))
      (node (ref "IC2") (pin "C1") (pinfunction "SCL_C1") (pintype "bidirectional"))
      (node (ref "IC3") (pin "12") (pinfunction "SCX_12") (pintype "bidirectional"))
      (node (ref "R17") (pin "2") (pinfunction "2_2") (pintype "bidirectional"))
      (node (ref "R4") (pin "1") (pinfunction "1_1") (pintype "bidirectional"))
      (node (ref "TP_SCL") (pin "TP") (pinfunction "TP_TP") (pintype "input"))
      (node (ref "U1") (pin "P$M2") (pinfunction "P0.07_P$M2") (pintype "bidirectional"))
      (node (ref "U3") (pin "7") (pinfunction "SCL_7") (pintype "input"))
    )
    (net (code "91") (name "SDA") (class "Default")
      (node (ref "IC1") (pin "C1") (pinfunction "SDA_C1") (pintype "bidirectional"))
      (node (ref "IC2") (pin "B2") (pinfunction "SDA_B2") (pintype "bidirectional"))
      (node (ref "IC3") (pin "2") (pinfunction "SDX_2") (pintype "bidirectional"))
      (node (ref "R18") (pin "2") (pinfunction "2_2") (pintype "bidirectional"))
      (node (ref "R2") (pin "1") (pinfunction "1_1") (pintype "bidirectional"))
      (node (ref "TP_SDA") (pin "TP") (pinfunction "TP_TP") (pintype "input"))
      (node (ref "U1") (pin "P$L1") (pinfunction "P0.06_P$L1") (pintype "bidirectional"))
      (node (ref "U3") (pin "8") (pinfunction "SDA_8") (pintype "bidirectional"))
    )
    (net (code "92") (name "SWDCLK") (class "Default")
      (node (ref "J2") (pin "4") (pinfunction "4_4") (pintype "bidirectional"))
      (node (ref "TP_SWDCLK") (pin "TP") (pinfunction "TP_TP") (pintype "input"))
      (node (ref "U1") (pin "P$AA24") (pinfunction "SWDCLK_P$AA24") (pintype "input"))
    )
    (net (code "93") (name "SWDIO") (class "Default")
      (node (ref "J2") (pin "2") (pinfunction "2_2") (pintype "bidirectional"))
      (node (ref "TP_SWDIO") (pin "TP") (pinfunction "TP_TP") (pintype "input"))
      (node (ref "U1") (pin "P$AC24") (pinfunction "SWDIO_P$AC24") (pintype "bidirectional"))
    )
    (net (code "94") (name "SWO") (class "Default")
      (node (ref "TP_SWO") (pin "TP") (pinfunction "TP_TP") (pintype "input"))
      (node (ref "U1") (pin "P$AD22") (pinfunction "P1.00_P$AD22") (pintype "bidirectional"))
    )
    (net (code "95") (name "VBAT") (class "Default")
      (node (ref "C27") (pin "2") (pinfunction "2_2") (pintype "passive"))
      (node (ref "C37") (pin "2") (pinfunction "2_2") (pintype "passive"))
      (node (ref "IC1") (pin "C2") (pinfunction "BAT_C2") (pintype "bidirectional"))
      (node (ref "TP_VBAT") (pin "TP") (pinfunction "TP_TP") (pintype "input"))
      (node (ref "U3") (pin "2") (pinfunction "CELL_2") (pintype "power_in"))
      (node (ref "U3") (pin "3") (pinfunction "VDD_3") (pintype "power_in"))
    )
    (net (code "96") (name "VBUS") (class "Default")
      (node (ref "C21") (pin "1") (pinfunction "1_1") (pintype "passive"))
      (node (ref "C38") (pin "2") (pinfunction "2_2") (pintype "passive"))
      (node (ref "C42") (pin "1") (pinfunction "1_1") (pintype "passive"))
      (node (ref "C43") (pin "1") (pinfunction "1_1") (pintype "passive"))
      (node (ref "D3") (pin "5") (pinfunction "VBUS_5") (pintype "bidirectional"))
      (node (ref "IC1") (pin "A2") (pinfunction "IN_A2") (pintype "bidirectional"))
      (node (ref "J4") (pin "A4_B9") (pinfunction "VBUS_A4_B9") (pintype "power_in"))
      (node (ref "J4") (pin "A9_B4") (pinfunction "VBUS_A9_B4") (pintype "power_in"))
      (node (ref "U1") (pin "P$AD2") (pinfunction "VBUS_P$AD2") (pintype "power_in"))
    )
    (net (code "97") (name "VREG") (class "Default")
      (node (ref "C23") (pin "1") (pinfunction "1_1") (pintype "passive"))
      (node (ref "C24") (pin "2") (pinfunction "2_2") (pintype "passive"))
      (node (ref "C39") (pin "1") (pinfunction "1_1") (pintype "passive"))
      (node (ref "IC1") (pin "B2") (pinfunction "SYS_B2") (pintype "bidirectional"))
      (node (ref "IC9") (pin "A1") (pinfunction "EN_A1") (pintype "bidirectional"))
      (node (ref "IC9") (pin "A2") (pinfunction "VIN_1_A2") (pintype "bidirectional"))
      (node (ref "IC9") (pin "A3") (pinfunction "VIN_2_A3") (pintype "bidirectional"))
      (node (ref "TP_VREG") (pin "TP") (pinfunction "TP_TP") (pintype "input"))
    )
    (net (code "98") (name "unconnected-(ANT1-NC-Pad2)") (class "Default")
      (node (ref "ANT1") (pin "2") (pinfunction "NC_2") (pintype "no_connect"))
    )
    (net (code "99") (name "unconnected-(IC3-ASCL-Pad11)") (class "Default")
      (node (ref "IC3") (pin "11") (pinfunction "ASCL_11") (pintype "bidirectional"))
    )
    (net (code "100") (name "unconnected-(IC3-ASDA-Pad4)") (class "Default")
      (node (ref "IC3") (pin "4") (pinfunction "ASDA_4") (pintype "bidirectional"))
    )
    (net (code "101") (name "unconnected-(J1-Pad1)") (class "Default")
      (node (ref "J1") (pin "1") (pinfunction "1_1") (pintype "bidirectional"))
    )
    (net (code "102") (name "unconnected-(J1-Pad6)") (class "Default")
      (node (ref "J1") (pin "6") (pinfunction "6_6") (pintype "bidirectional"))
    )
    (net (code "103") (name "unconnected-(J1-Pad7)") (class "Default")
      (node (ref "J1") (pin "7") (pinfunction "7_7") (pintype "bidirectional"))
    )
    (net (code "104") (name "unconnected-(J4-SBU1-PadA8)") (class "Default")
      (node (ref "J4") (pin "A8") (pinfunction "SBU1_A8") (pintype "bidirectional"))
    )
    (net (code "105") (name "unconnected-(J4-SBU2-PadB8)") (class "Default")
      (node (ref "J4") (pin "B8") (pinfunction "SBU2_B8") (pintype "bidirectional"))
    )
    (net (code "106") (name "unconnected-(U1-DCCH-PadP$AB2)") (class "Default")
      (node (ref "U1") (pin "P$AB2") (pinfunction "DCCH_P$AB2") (pintype "bidirectional"))
    )
  )
)
